# PCB-AC4.net
KiCad netlist of a schematic drawn in EAGLE
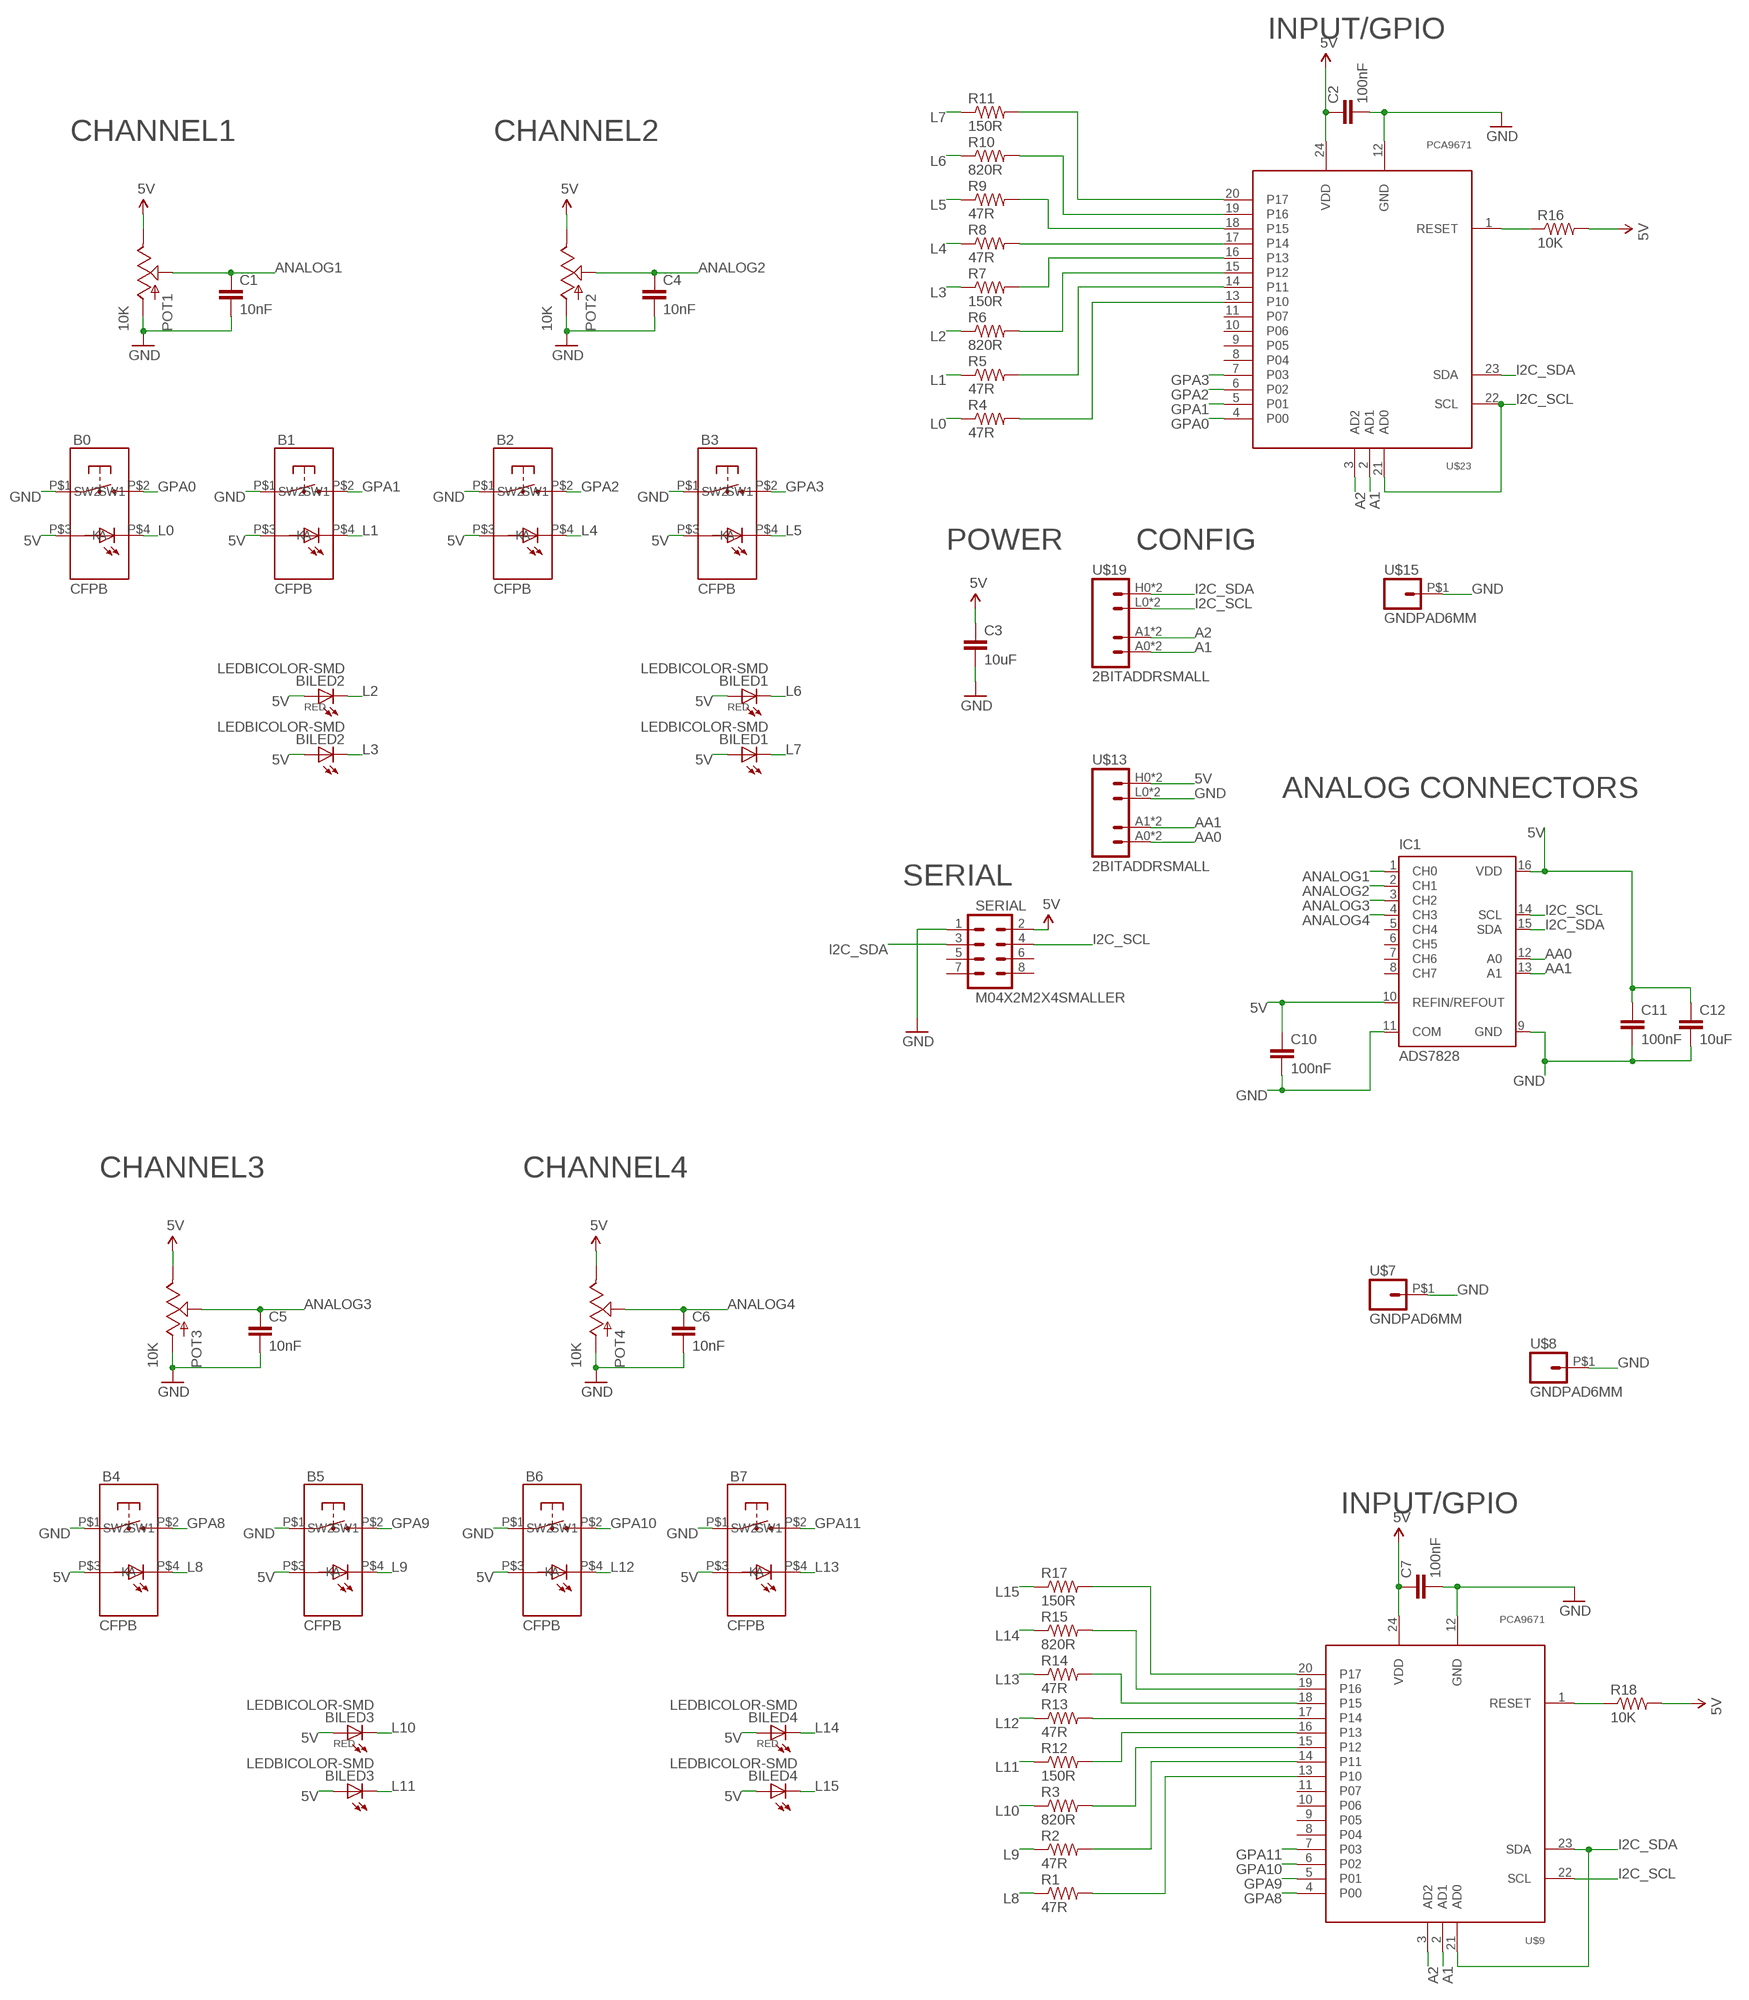
[diagram p0: schematic, sheet 1]

(export (version "E")
  (design (tool "Eeschema 10.0.6"))
  (components
    (comp (ref "B0")
      (value "CFPB")
      (footprint "eagle-import:CFPB-6_9MM")
      (libsource (lib "eagle-import") (part "CFPB"))
    )
    (comp (ref "B1")
      (value "CFPB")
      (footprint "eagle-import:CFPB-6_9MM")
      (libsource (lib "eagle-import") (part "CFPB"))
    )
    (comp (ref "B2")
      (value "CFPB")
      (footprint "eagle-import:CFPB-6_9MM")
      (libsource (lib "eagle-import") (part "CFPB"))
    )
    (comp (ref "B3")
      (value "CFPB")
      (footprint "eagle-import:CFPB-6_9MM")
      (libsource (lib "eagle-import") (part "CFPB"))
    )
    (comp (ref "B4")
      (value "CFPB")
      (footprint "eagle-import:CFPB-6_9MM")
      (libsource (lib "eagle-import") (part "CFPB"))
    )
    (comp (ref "B5")
      (value "CFPB")
      (footprint "eagle-import:CFPB-6_9MM")
      (libsource (lib "eagle-import") (part "CFPB"))
    )
    (comp (ref "B6")
      (value "CFPB")
      (footprint "eagle-import:CFPB-6_9MM")
      (libsource (lib "eagle-import") (part "CFPB"))
    )
    (comp (ref "B7")
      (value "CFPB")
      (footprint "eagle-import:CFPB-6_9MM")
      (libsource (lib "eagle-import") (part "CFPB"))
    )
    (comp (ref "BILED1")
      (value "LEDBICOLOR-SMD")
      (footprint "eagle-import:LEDBICOLOR-SMD")
      (libsource (lib "eagle-import") (part "LEDBICOLOR-SMD"))
    )
    (comp (ref "BILED2")
      (value "LEDBICOLOR-SMD")
      (footprint "eagle-import:LEDBICOLOR-SMD")
      (libsource (lib "eagle-import") (part "LEDBICOLOR-SMD"))
    )
    (comp (ref "BILED3")
      (value "LEDBICOLOR-SMD")
      (footprint "eagle-import:LEDBICOLOR-SMD")
      (libsource (lib "eagle-import") (part "LEDBICOLOR-SMD"))
    )
    (comp (ref "BILED4")
      (value "LEDBICOLOR-SMD")
      (footprint "eagle-import:LEDBICOLOR-SMD")
      (libsource (lib "eagle-import") (part "LEDBICOLOR-SMD"))
    )
    (comp (ref "C1")
      (value "10nF")
      (footprint "eagle-import:0603-CAP")
      (libsource (lib "eagle-import") (part "CAP0603-CAP"))
    )
    (comp (ref "C2")
      (value "100nF")
      (footprint "eagle-import:0603-CAP")
      (libsource (lib "eagle-import") (part "CAP0603-CAP"))
    )
    (comp (ref "C3")
      (value "10uF")
      (footprint "eagle-import:0805")
      (libsource (lib "eagle-import") (part "CAP0805"))
    )
    (comp (ref "C4")
      (value "10nF")
      (footprint "eagle-import:0603-CAP")
      (libsource (lib "eagle-import") (part "CAP0603-CAP"))
    )
    (comp (ref "C5")
      (value "10nF")
      (footprint "eagle-import:0603-CAP")
      (libsource (lib "eagle-import") (part "CAP0603-CAP"))
    )
    (comp (ref "C6")
      (value "10nF")
      (footprint "eagle-import:0603-CAP")
      (libsource (lib "eagle-import") (part "CAP0603-CAP"))
    )
    (comp (ref "C7")
      (value "100nF")
      (footprint "eagle-import:0603-CAP")
      (libsource (lib "eagle-import") (part "CAP0603-CAP"))
    )
    (comp (ref "C10")
      (value "100nF")
      (footprint "eagle-import:0603-CAP")
      (libsource (lib "eagle-import") (part "CAP0603-CAP"))
    )
    (comp (ref "C11")
      (value "100nF")
      (footprint "eagle-import:0603-CAP")
      (libsource (lib "eagle-import") (part "CAP0603-CAP"))
    )
    (comp (ref "C12")
      (value "10uF")
      (footprint "eagle-import:0805")
      (libsource (lib "eagle-import") (part "CAP0805"))
    )
    (comp (ref "IC1")
      (value "ADS7828")
      (footprint "eagle-import:TSSOP16-PW")
      (fields (field (name "MF") "TEXAS INSTRUMENTS") (field (name "MPN") "ADS7828E/250"))
      (libsource (lib "eagle-import") (part "ADS7828"))
    )
    (comp (ref "POT1")
      (value "10K")
      (footprint "eagle-import:ALPS_POT")
      (libsource (lib "eagle-import") (part "POT"))
    )
    (comp (ref "POT2")
      (value "10K")
      (footprint "eagle-import:ALPS_POT")
      (libsource (lib "eagle-import") (part "POT"))
    )
    (comp (ref "POT3")
      (value "10K")
      (footprint "eagle-import:ALPS_POT")
      (libsource (lib "eagle-import") (part "POT"))
    )
    (comp (ref "POT4")
      (value "10K")
      (footprint "eagle-import:ALPS_POT")
      (libsource (lib "eagle-import") (part "POT"))
    )
    (comp (ref "R1")
      (value "47R")
      (footprint "eagle-import:0603-RES")
      (libsource (lib "eagle-import") (part "RESISTOR0603-RES"))
    )
    (comp (ref "R2")
      (value "47R")
      (footprint "eagle-import:0603-RES")
      (libsource (lib "eagle-import") (part "RESISTOR0603-RES"))
    )
    (comp (ref "R3")
      (value "820R")
      (footprint "eagle-import:0603-RES")
      (libsource (lib "eagle-import") (part "RESISTOR0603-RES"))
    )
    (comp (ref "R4")
      (value "47R")
      (footprint "eagle-import:0603-RES")
      (libsource (lib "eagle-import") (part "RESISTOR0603-RES"))
    )
    (comp (ref "R5")
      (value "47R")
      (footprint "eagle-import:0603-RES")
      (libsource (lib "eagle-import") (part "RESISTOR0603-RES"))
    )
    (comp (ref "R6")
      (value "820R")
      (footprint "eagle-import:0603-RES")
      (libsource (lib "eagle-import") (part "RESISTOR0603-RES"))
    )
    (comp (ref "R7")
      (value "150R")
      (footprint "eagle-import:0603-RES")
      (libsource (lib "eagle-import") (part "RESISTOR0603-RES"))
    )
    (comp (ref "R8")
      (value "47R")
      (footprint "eagle-import:0603-RES")
      (libsource (lib "eagle-import") (part "RESISTOR0603-RES"))
    )
    (comp (ref "R9")
      (value "47R")
      (footprint "eagle-import:0603-RES")
      (libsource (lib "eagle-import") (part "RESISTOR0603-RES"))
    )
    (comp (ref "R10")
      (value "820R")
      (footprint "eagle-import:0603-RES")
      (libsource (lib "eagle-import") (part "RESISTOR0603-RES"))
    )
    (comp (ref "R11")
      (value "150R")
      (footprint "eagle-import:0603-RES")
      (libsource (lib "eagle-import") (part "RESISTOR0603-RES"))
    )
    (comp (ref "R12")
      (value "150R")
      (footprint "eagle-import:0603-RES")
      (libsource (lib "eagle-import") (part "RESISTOR0603-RES"))
    )
    (comp (ref "R13")
      (value "47R")
      (footprint "eagle-import:0603-RES")
      (libsource (lib "eagle-import") (part "RESISTOR0603-RES"))
    )
    (comp (ref "R14")
      (value "47R")
      (footprint "eagle-import:0603-RES")
      (libsource (lib "eagle-import") (part "RESISTOR0603-RES"))
    )
    (comp (ref "R15")
      (value "820R")
      (footprint "eagle-import:0603-RES")
      (libsource (lib "eagle-import") (part "RESISTOR0603-RES"))
    )
    (comp (ref "R16")
      (value "10K")
      (footprint "eagle-import:0603-RES")
      (libsource (lib "eagle-import") (part "RESISTOR0603-RES"))
    )
    (comp (ref "R17")
      (value "150R")
      (footprint "eagle-import:0603-RES")
      (libsource (lib "eagle-import") (part "RESISTOR0603-RES"))
    )
    (comp (ref "R18")
      (value "10K")
      (footprint "eagle-import:0603-RES")
      (libsource (lib "eagle-import") (part "RESISTOR0603-RES"))
    )
    (comp (ref "SERIAL")
      (value "M04X2M2X4SMALLER")
      (footprint "eagle-import:M2X4SMALLER")
      (libsource (lib "eagle-import") (part "M04X2M2X4SMALLER"))
    )
    (comp (ref "U$7")
      (value "GNDPAD6MM")
      (footprint "eagle-import:3.2MMPAD6MM")
      (libsource (lib "eagle-import") (part "GNDPAD6MM"))
    )
    (comp (ref "U$8")
      (value "GNDPAD6MM")
      (footprint "eagle-import:3.2MMPAD6MM")
      (libsource (lib "eagle-import") (part "GNDPAD6MM"))
    )
    (comp (ref "U$9")
      (value "PCA9671")
      (footprint "eagle-import:TSSOP24")
      (libsource (lib "eagle-import") (part "PCA9671"))
    )
    (comp (ref "U$13")
      (value "2BITADDRSMALL")
      (footprint "eagle-import:2BITADDR_SMALL")
      (libsource (lib "eagle-import") (part "2BITADDRSMALL"))
    )
    (comp (ref "U$15")
      (value "GNDPAD6MM")
      (footprint "eagle-import:3.2MMPAD6MM")
      (libsource (lib "eagle-import") (part "GNDPAD6MM"))
    )
    (comp (ref "U$19")
      (value "2BITADDRSMALL")
      (footprint "eagle-import:2BITADDR_SMALL")
      (libsource (lib "eagle-import") (part "2BITADDRSMALL"))
    )
    (comp (ref "U$23")
      (value "PCA9671")
      (footprint "eagle-import:TSSOP24")
      (libsource (lib "eagle-import") (part "PCA9671"))
    )
  )
  (nets
    (net (code "1") (name "5V") (class "Default")
      (node (ref "B0") (pin "P$3") (pinfunction "A_P$3") (pintype "bidirectional"))
      (node (ref "B1") (pin "P$3") (pinfunction "A_P$3") (pintype "bidirectional"))
      (node (ref "B2") (pin "P$3") (pinfunction "A_P$3") (pintype "bidirectional"))
      (node (ref "B3") (pin "P$3") (pinfunction "A_P$3") (pintype "bidirectional"))
      (node (ref "B4") (pin "P$3") (pinfunction "A_P$3") (pintype "bidirectional"))
      (node (ref "B5") (pin "P$3") (pinfunction "A_P$3") (pintype "bidirectional"))
      (node (ref "B6") (pin "P$3") (pinfunction "A_P$3") (pintype "bidirectional"))
      (node (ref "B7") (pin "P$3") (pinfunction "A_P$3") (pintype "bidirectional"))
      (node (ref "BILED1") (pin "P$1") (pinfunction "A_P$1") (pintype "passive"))
      (node (ref "BILED1") (pin "P$3") (pinfunction "A1_P$3") (pintype "passive"))
      (node (ref "BILED2") (pin "P$1") (pinfunction "A_P$1") (pintype "passive"))
      (node (ref "BILED2") (pin "P$3") (pinfunction "A1_P$3") (pintype "passive"))
      (node (ref "BILED3") (pin "P$1") (pinfunction "A_P$1") (pintype "passive"))
      (node (ref "BILED3") (pin "P$3") (pinfunction "A1_P$3") (pintype "passive"))
      (node (ref "BILED4") (pin "P$1") (pinfunction "A_P$1") (pintype "passive"))
      (node (ref "BILED4") (pin "P$3") (pinfunction "A1_P$3") (pintype "passive"))
      (node (ref "C10") (pin "1") (pinfunction "1_1") (pintype "passive"))
      (node (ref "C11") (pin "1") (pinfunction "1_1") (pintype "passive"))
      (node (ref "C12") (pin "1") (pinfunction "1_1") (pintype "passive"))
      (node (ref "C2") (pin "1") (pinfunction "1_1") (pintype "passive"))
      (node (ref "C3") (pin "1") (pinfunction "1_1") (pintype "passive"))
      (node (ref "C7") (pin "1") (pinfunction "1_1") (pintype "passive"))
      (node (ref "IC1") (pin "10") (pinfunction "REFIN/REFOUT_10") (pintype "passive"))
      (node (ref "IC1") (pin "16") (pinfunction "VDD_16") (pintype "power_in"))
      (node (ref "POT1") (pin "P$1") (pinfunction "E_P$1") (pintype "passive"))
      (node (ref "POT2") (pin "P$1") (pinfunction "E_P$1") (pintype "passive"))
      (node (ref "POT3") (pin "P$1") (pinfunction "E_P$1") (pintype "passive"))
      (node (ref "POT4") (pin "P$1") (pinfunction "E_P$1") (pintype "passive"))
      (node (ref "R16") (pin "2") (pinfunction "2_2") (pintype "passive"))
      (node (ref "R18") (pin "2") (pinfunction "2_2") (pintype "passive"))
      (node (ref "SERIAL") (pin "2") (pinfunction "2_2") (pintype "passive"))
      (node (ref "U$13") (pin "H0") (pinfunction "VCC_H0") (pintype "passive"))
      (node (ref "U$13") (pin "H1") (pinfunction "VCC_H1") (pintype "passive"))
      (node (ref "U$23") (pin "24") (pinfunction "VDD_24") (pintype "power_in"))
      (node (ref "U$9") (pin "24") (pinfunction "VDD_24") (pintype "power_in"))
    )
    (net (code "2") (name "A1") (class "Default")
      (node (ref "U$19") (pin "A0") (pinfunction "A1_A0") (pintype "passive"))
      (node (ref "U$19") (pin "AS0") (pinfunction "A1_AS0") (pintype "passive"))
      (node (ref "U$23") (pin "2") (pinfunction "AD1_2") (pintype "input"))
      (node (ref "U$9") (pin "2") (pinfunction "AD1_2") (pintype "input"))
    )
    (net (code "3") (name "A2") (class "Default")
      (node (ref "U$19") (pin "A1") (pinfunction "A2_A1") (pintype "passive"))
      (node (ref "U$19") (pin "AS1") (pinfunction "A2_AS1") (pintype "passive"))
      (node (ref "U$23") (pin "3") (pinfunction "AD2_3") (pintype "input"))
      (node (ref "U$9") (pin "3") (pinfunction "AD2_3") (pintype "input"))
    )
    (net (code "4") (name "AA0") (class "Default")
      (node (ref "IC1") (pin "12") (pinfunction "A0_12") (pintype "input"))
      (node (ref "U$13") (pin "A0") (pinfunction "A1_A0") (pintype "passive"))
      (node (ref "U$13") (pin "AS0") (pinfunction "A1_AS0") (pintype "passive"))
    )
    (net (code "5") (name "AA1") (class "Default")
      (node (ref "IC1") (pin "13") (pinfunction "A1_13") (pintype "input"))
      (node (ref "U$13") (pin "A1") (pinfunction "A2_A1") (pintype "passive"))
      (node (ref "U$13") (pin "AS1") (pinfunction "A2_AS1") (pintype "passive"))
    )
    (net (code "6") (name "ANALOG1") (class "Default")
      (node (ref "C1") (pin "1") (pinfunction "1_1") (pintype "passive"))
      (node (ref "IC1") (pin "1") (pinfunction "CH0_1") (pintype "input"))
      (node (ref "POT1") (pin "P$2") (pinfunction "S_P$2") (pintype "passive"))
    )
    (net (code "7") (name "ANALOG2") (class "Default")
      (node (ref "C4") (pin "1") (pinfunction "1_1") (pintype "passive"))
      (node (ref "IC1") (pin "2") (pinfunction "CH1_2") (pintype "input"))
      (node (ref "POT2") (pin "P$2") (pinfunction "S_P$2") (pintype "passive"))
    )
    (net (code "8") (name "ANALOG3") (class "Default")
      (node (ref "C5") (pin "1") (pinfunction "1_1") (pintype "passive"))
      (node (ref "IC1") (pin "3") (pinfunction "CH2_3") (pintype "input"))
      (node (ref "POT3") (pin "P$2") (pinfunction "S_P$2") (pintype "passive"))
    )
    (net (code "9") (name "ANALOG4") (class "Default")
      (node (ref "C6") (pin "1") (pinfunction "1_1") (pintype "passive"))
      (node (ref "IC1") (pin "4") (pinfunction "CH3_4") (pintype "input"))
      (node (ref "POT4") (pin "P$2") (pinfunction "S_P$2") (pintype "passive"))
    )
    (net (code "10") (name "GND") (class "Default")
      (node (ref "B0") (pin "P$1") (pinfunction "SW1_P$1") (pintype "bidirectional"))
      (node (ref "B1") (pin "P$1") (pinfunction "SW1_P$1") (pintype "bidirectional"))
      (node (ref "B2") (pin "P$1") (pinfunction "SW1_P$1") (pintype "bidirectional"))
      (node (ref "B3") (pin "P$1") (pinfunction "SW1_P$1") (pintype "bidirectional"))
      (node (ref "B4") (pin "P$1") (pinfunction "SW1_P$1") (pintype "bidirectional"))
      (node (ref "B5") (pin "P$1") (pinfunction "SW1_P$1") (pintype "bidirectional"))
      (node (ref "B6") (pin "P$1") (pinfunction "SW1_P$1") (pintype "bidirectional"))
      (node (ref "B7") (pin "P$1") (pinfunction "SW1_P$1") (pintype "bidirectional"))
      (node (ref "C1") (pin "2") (pinfunction "2_2") (pintype "passive"))
      (node (ref "C10") (pin "2") (pinfunction "2_2") (pintype "passive"))
      (node (ref "C11") (pin "2") (pinfunction "2_2") (pintype "passive"))
      (node (ref "C12") (pin "2") (pinfunction "2_2") (pintype "passive"))
      (node (ref "C2") (pin "2") (pinfunction "2_2") (pintype "passive"))
      (node (ref "C3") (pin "2") (pinfunction "2_2") (pintype "passive"))
      (node (ref "C4") (pin "2") (pinfunction "2_2") (pintype "passive"))
      (node (ref "C5") (pin "2") (pinfunction "2_2") (pintype "passive"))
      (node (ref "C6") (pin "2") (pinfunction "2_2") (pintype "passive"))
      (node (ref "C7") (pin "2") (pinfunction "2_2") (pintype "passive"))
      (node (ref "IC1") (pin "11") (pinfunction "COM_11") (pintype "input"))
      (node (ref "IC1") (pin "9") (pinfunction "GND_9") (pintype "power_in"))
      (node (ref "POT1") (pin "P$3") (pinfunction "A_P$3") (pintype "passive"))
      (node (ref "POT2") (pin "P$3") (pinfunction "A_P$3") (pintype "passive"))
      (node (ref "POT3") (pin "P$3") (pinfunction "A_P$3") (pintype "passive"))
      (node (ref "POT4") (pin "P$3") (pinfunction "A_P$3") (pintype "passive"))
      (node (ref "SERIAL") (pin "1") (pinfunction "1_1") (pintype "passive"))
      (node (ref "U$13") (pin "L0") (pinfunction "GND_L0") (pintype "passive"))
      (node (ref "U$13") (pin "L1") (pinfunction "GND_L1") (pintype "passive"))
      (node (ref "U$15") (pin "P$1") (pinfunction "1_P$1") (pintype "passive"))
      (node (ref "U$23") (pin "12") (pinfunction "GND_12") (pintype "power_in"))
      (node (ref "U$7") (pin "P$1") (pinfunction "1_P$1") (pintype "passive"))
      (node (ref "U$8") (pin "P$1") (pinfunction "1_P$1") (pintype "passive"))
      (node (ref "U$9") (pin "12") (pinfunction "GND_12") (pintype "power_in"))
    )
    (net (code "11") (name "GPA0") (class "Default")
      (node (ref "B0") (pin "P$2") (pinfunction "SW2_P$2") (pintype "bidirectional"))
      (node (ref "U$23") (pin "4") (pinfunction "P00_4") (pintype "output"))
    )
    (net (code "12") (name "GPA1") (class "Default")
      (node (ref "B1") (pin "P$2") (pinfunction "SW2_P$2") (pintype "bidirectional"))
      (node (ref "U$23") (pin "5") (pinfunction "P01_5") (pintype "output"))
    )
    (net (code "13") (name "GPA2") (class "Default")
      (node (ref "B2") (pin "P$2") (pinfunction "SW2_P$2") (pintype "bidirectional"))
      (node (ref "U$23") (pin "6") (pinfunction "P02_6") (pintype "output"))
    )
    (net (code "14") (name "GPA3") (class "Default")
      (node (ref "B3") (pin "P$2") (pinfunction "SW2_P$2") (pintype "bidirectional"))
      (node (ref "U$23") (pin "7") (pinfunction "P03_7") (pintype "output"))
    )
    (net (code "15") (name "GPA8") (class "Default")
      (node (ref "B4") (pin "P$2") (pinfunction "SW2_P$2") (pintype "bidirectional"))
      (node (ref "U$9") (pin "4") (pinfunction "P00_4") (pintype "output"))
    )
    (net (code "16") (name "GPA9") (class "Default")
      (node (ref "B5") (pin "P$2") (pinfunction "SW2_P$2") (pintype "bidirectional"))
      (node (ref "U$9") (pin "5") (pinfunction "P01_5") (pintype "output"))
    )
    (net (code "17") (name "GPA10") (class "Default")
      (node (ref "B6") (pin "P$2") (pinfunction "SW2_P$2") (pintype "bidirectional"))
      (node (ref "U$9") (pin "6") (pinfunction "P02_6") (pintype "output"))
    )
    (net (code "18") (name "GPA11") (class "Default")
      (node (ref "B7") (pin "P$2") (pinfunction "SW2_P$2") (pintype "bidirectional"))
      (node (ref "U$9") (pin "7") (pinfunction "P03_7") (pintype "output"))
    )
    (net (code "19") (name "I2C_SCL") (class "Default")
      (node (ref "IC1") (pin "14") (pinfunction "SCL_14") (pintype "input"))
      (node (ref "SERIAL") (pin "4") (pinfunction "4_4") (pintype "passive"))
      (node (ref "U$19") (pin "L0") (pinfunction "GND_L0") (pintype "passive"))
      (node (ref "U$19") (pin "L1") (pinfunction "GND_L1") (pintype "passive"))
      (node (ref "U$23") (pin "21") (pinfunction "AD0_21") (pintype "input"))
      (node (ref "U$23") (pin "22") (pinfunction "SCL_22") (pintype "input"))
      (node (ref "U$9") (pin "22") (pinfunction "SCL_22") (pintype "input"))
    )
    (net (code "20") (name "I2C_SDA") (class "Default")
      (node (ref "IC1") (pin "15") (pinfunction "SDA_15") (pintype "bidirectional"))
      (node (ref "SERIAL") (pin "3") (pinfunction "3_3") (pintype "passive"))
      (node (ref "U$19") (pin "H0") (pinfunction "VCC_H0") (pintype "passive"))
      (node (ref "U$19") (pin "H1") (pinfunction "VCC_H1") (pintype "passive"))
      (node (ref "U$23") (pin "23") (pinfunction "SDA_23") (pintype "input"))
      (node (ref "U$9") (pin "21") (pinfunction "AD0_21") (pintype "input"))
      (node (ref "U$9") (pin "23") (pinfunction "SDA_23") (pintype "input"))
    )
    (net (code "21") (name "L0") (class "Default")
      (node (ref "B0") (pin "P$4") (pinfunction "K_P$4") (pintype "bidirectional"))
      (node (ref "R4") (pin "1") (pinfunction "1_1") (pintype "passive"))
    )
    (net (code "22") (name "L1") (class "Default")
      (node (ref "B1") (pin "P$4") (pinfunction "K_P$4") (pintype "bidirectional"))
      (node (ref "R5") (pin "1") (pinfunction "1_1") (pintype "passive"))
    )
    (net (code "23") (name "L2") (class "Default")
      (node (ref "BILED2") (pin "P$2") (pinfunction "C_P$2") (pintype "passive"))
      (node (ref "R6") (pin "1") (pinfunction "1_1") (pintype "passive"))
    )
    (net (code "24") (name "L3") (class "Default")
      (node (ref "BILED2") (pin "P$4") (pinfunction "C1_P$4") (pintype "passive"))
      (node (ref "R7") (pin "1") (pinfunction "1_1") (pintype "passive"))
    )
    (net (code "25") (name "L4") (class "Default")
      (node (ref "B2") (pin "P$4") (pinfunction "K_P$4") (pintype "bidirectional"))
      (node (ref "R8") (pin "1") (pinfunction "1_1") (pintype "passive"))
    )
    (net (code "26") (name "L5") (class "Default")
      (node (ref "B3") (pin "P$4") (pinfunction "K_P$4") (pintype "bidirectional"))
      (node (ref "R9") (pin "1") (pinfunction "1_1") (pintype "passive"))
    )
    (net (code "27") (name "L6") (class "Default")
      (node (ref "BILED1") (pin "P$2") (pinfunction "C_P$2") (pintype "passive"))
      (node (ref "R10") (pin "1") (pinfunction "1_1") (pintype "passive"))
    )
    (net (code "28") (name "L7") (class "Default")
      (node (ref "BILED1") (pin "P$4") (pinfunction "C1_P$4") (pintype "passive"))
      (node (ref "R11") (pin "1") (pinfunction "1_1") (pintype "passive"))
    )
    (net (code "29") (name "L8") (class "Default")
      (node (ref "B4") (pin "P$4") (pinfunction "K_P$4") (pintype "bidirectional"))
      (node (ref "R1") (pin "1") (pinfunction "1_1") (pintype "passive"))
    )
    (net (code "30") (name "L9") (class "Default")
      (node (ref "B5") (pin "P$4") (pinfunction "K_P$4") (pintype "bidirectional"))
      (node (ref "R2") (pin "1") (pinfunction "1_1") (pintype "passive"))
    )
    (net (code "31") (name "L10") (class "Default")
      (node (ref "BILED3") (pin "P$2") (pinfunction "C_P$2") (pintype "passive"))
      (node (ref "R3") (pin "1") (pinfunction "1_1") (pintype "passive"))
    )
    (net (code "32") (name "L11") (class "Default")
      (node (ref "BILED3") (pin "P$4") (pinfunction "C1_P$4") (pintype "passive"))
      (node (ref "R12") (pin "1") (pinfunction "1_1") (pintype "passive"))
    )
    (net (code "33") (name "L12") (class "Default")
      (node (ref "B6") (pin "P$4") (pinfunction "K_P$4") (pintype "bidirectional"))
      (node (ref "R13") (pin "1") (pinfunction "1_1") (pintype "passive"))
    )
    (net (code "34") (name "L13") (class "Default")
      (node (ref "B7") (pin "P$4") (pinfunction "K_P$4") (pintype "bidirectional"))
      (node (ref "R14") (pin "1") (pinfunction "1_1") (pintype "passive"))
    )
    (net (code "35") (name "L14") (class "Default")
      (node (ref "BILED4") (pin "P$2") (pinfunction "C_P$2") (pintype "passive"))
      (node (ref "R15") (pin "1") (pinfunction "1_1") (pintype "passive"))
    )
    (net (code "36") (name "L15") (class "Default")
      (node (ref "BILED4") (pin "P$4") (pinfunction "C1_P$4") (pintype "passive"))
      (node (ref "R17") (pin "1") (pinfunction "1_1") (pintype "passive"))
    )
    (net (code "37") (name "Net-(U$9-P10)") (class "Default")
      (node (ref "R1") (pin "2") (pinfunction "2_2") (pintype "passive"))
      (node (ref "U$9") (pin "13") (pinfunction "P10_13") (pintype "output"))
    )
    (net (code "38") (name "Net-(U$9-P11)") (class "Default")
      (node (ref "R2") (pin "2") (pinfunction "2_2") (pintype "passive"))
      (node (ref "U$9") (pin "14") (pinfunction "P11_14") (pintype "output"))
    )
    (net (code "39") (name "Net-(U$9-P12)") (class "Default")
      (node (ref "R3") (pin "2") (pinfunction "2_2") (pintype "passive"))
      (node (ref "U$9") (pin "15") (pinfunction "P12_15") (pintype "output"))
    )
    (net (code "40") (name "Net-(U$9-P13)") (class "Default")
      (node (ref "R12") (pin "2") (pinfunction "2_2") (pintype "passive"))
      (node (ref "U$9") (pin "16") (pinfunction "P13_16") (pintype "output"))
    )
    (net (code "41") (name "Net-(U$9-P14)") (class "Default")
      (node (ref "R13") (pin "2") (pinfunction "2_2") (pintype "passive"))
      (node (ref "U$9") (pin "17") (pinfunction "P14_17") (pintype "output"))
    )
    (net (code "42") (name "Net-(U$9-P15)") (class "Default")
      (node (ref "R14") (pin "2") (pinfunction "2_2") (pintype "passive"))
      (node (ref "U$9") (pin "18") (pinfunction "P15_18") (pintype "output"))
    )
    (net (code "43") (name "Net-(U$9-P16)") (class "Default")
      (node (ref "R15") (pin "2") (pinfunction "2_2") (pintype "passive"))
      (node (ref "U$9") (pin "19") (pinfunction "P16_19") (pintype "output"))
    )
    (net (code "44") (name "Net-(U$9-P17)") (class "Default")
      (node (ref "R17") (pin "2") (pinfunction "2_2") (pintype "passive"))
      (node (ref "U$9") (pin "20") (pinfunction "P17_20") (pintype "output"))
    )
    (net (code "45") (name "Net-(U$9-RESET)") (class "Default")
      (node (ref "R18") (pin "1") (pinfunction "1_1") (pintype "passive"))
      (node (ref "U$9") (pin "1") (pinfunction "RESET_1") (pintype "input"))
    )
    (net (code "46") (name "Net-(U$23-P10)") (class "Default")
      (node (ref "R4") (pin "2") (pinfunction "2_2") (pintype "passive"))
      (node (ref "U$23") (pin "13") (pinfunction "P10_13") (pintype "output"))
    )
    (net (code "47") (name "Net-(U$23-P11)") (class "Default")
      (node (ref "R5") (pin "2") (pinfunction "2_2") (pintype "passive"))
      (node (ref "U$23") (pin "14") (pinfunction "P11_14") (pintype "output"))
    )
    (net (code "48") (name "Net-(U$23-P12)") (class "Default")
      (node (ref "R6") (pin "2") (pinfunction "2_2") (pintype "passive"))
      (node (ref "U$23") (pin "15") (pinfunction "P12_15") (pintype "output"))
    )
    (net (code "49") (name "Net-(U$23-P13)") (class "Default")
      (node (ref "R7") (pin "2") (pinfunction "2_2") (pintype "passive"))
      (node (ref "U$23") (pin "16") (pinfunction "P13_16") (pintype "output"))
    )
    (net (code "50") (name "Net-(U$23-P14)") (class "Default")
      (node (ref "R8") (pin "2") (pinfunction "2_2") (pintype "passive"))
      (node (ref "U$23") (pin "17") (pinfunction "P14_17") (pintype "output"))
    )
    (net (code "51") (name "Net-(U$23-P15)") (class "Default")
      (node (ref "R9") (pin "2") (pinfunction "2_2") (pintype "passive"))
      (node (ref "U$23") (pin "18") (pinfunction "P15_18") (pintype "output"))
    )
    (net (code "52") (name "Net-(U$23-P16)") (class "Default")
      (node (ref "R10") (pin "2") (pinfunction "2_2") (pintype "passive"))
      (node (ref "U$23") (pin "19") (pinfunction "P16_19") (pintype "output"))
    )
    (net (code "53") (name "Net-(U$23-P17)") (class "Default")
      (node (ref "R11") (pin "2") (pinfunction "2_2") (pintype "passive"))
      (node (ref "U$23") (pin "20") (pinfunction "P17_20") (pintype "output"))
    )
    (net (code "54") (name "Net-(U$23-RESET)") (class "Default")
      (node (ref "R16") (pin "1") (pinfunction "1_1") (pintype "passive"))
      (node (ref "U$23") (pin "1") (pinfunction "RESET_1") (pintype "input"))
    )
    (net (code "55") (name "unconnected-(IC1-CH4-Pad5)") (class "Default")
      (node (ref "IC1") (pin "5") (pinfunction "CH4_5") (pintype "input"))
    )
    (net (code "56") (name "unconnected-(IC1-CH5-Pad6)") (class "Default")
      (node (ref "IC1") (pin "6") (pinfunction "CH5_6") (pintype "input"))
    )
    (net (code "57") (name "unconnected-(IC1-CH6-Pad7)") (class "Default")
      (node (ref "IC1") (pin "7") (pinfunction "CH6_7") (pintype "input"))
    )
    (net (code "58") (name "unconnected-(IC1-CH7-Pad8)") (class "Default")
      (node (ref "IC1") (pin "8") (pinfunction "CH7_8") (pintype "input"))
    )
    (net (code "59") (name "unconnected-(SERIAL-Pad5)") (class "Default")
      (node (ref "SERIAL") (pin "5") (pinfunction "5_5") (pintype "passive"))
    )
    (net (code "60") (name "unconnected-(SERIAL-Pad6)") (class "Default")
      (node (ref "SERIAL") (pin "6") (pinfunction "6_6") (pintype "passive"))
    )
    (net (code "61") (name "unconnected-(SERIAL-Pad7)") (class "Default")
      (node (ref "SERIAL") (pin "7") (pinfunction "7_7") (pintype "passive"))
    )
    (net (code "62") (name "unconnected-(SERIAL-Pad8)") (class "Default")
      (node (ref "SERIAL") (pin "8") (pinfunction "8_8") (pintype "passive"))
    )
    (net (code "63") (name "unconnected-(U$9-P04-Pad8)") (class "Default")
      (node (ref "U$9") (pin "8") (pinfunction "P04_8") (pintype "output"))
    )
    (net (code "64") (name "unconnected-(U$9-P05-Pad9)") (class "Default")
      (node (ref "U$9") (pin "9") (pinfunction "P05_9") (pintype "output"))
    )
    (net (code "65") (name "unconnected-(U$9-P06-Pad10)") (class "Default")
      (node (ref "U$9") (pin "10") (pinfunction "P06_10") (pintype "output"))
    )
    (net (code "66") (name "unconnected-(U$9-P07-Pad11)") (class "Default")
      (node (ref "U$9") (pin "11") (pinfunction "P07_11") (pintype "output"))
    )
    (net (code "67") (name "unconnected-(U$23-P04-Pad8)") (class "Default")
      (node (ref "U$23") (pin "8") (pinfunction "P04_8") (pintype "output"))
    )
    (net (code "68") (name "unconnected-(U$23-P05-Pad9)") (class "Default")
      (node (ref "U$23") (pin "9") (pinfunction "P05_9") (pintype "output"))
    )
    (net (code "69") (name "unconnected-(U$23-P06-Pad10)") (class "Default")
      (node (ref "U$23") (pin "10") (pinfunction "P06_10") (pintype "output"))
    )
    (net (code "70") (name "unconnected-(U$23-P07-Pad11)") (class "Default")
      (node (ref "U$23") (pin "11") (pinfunction "P07_11") (pintype "output"))
    )
  )
)
